# Lights-ctrl_rev02.net
KiCad netlist of a schematic drawn in EAGLE
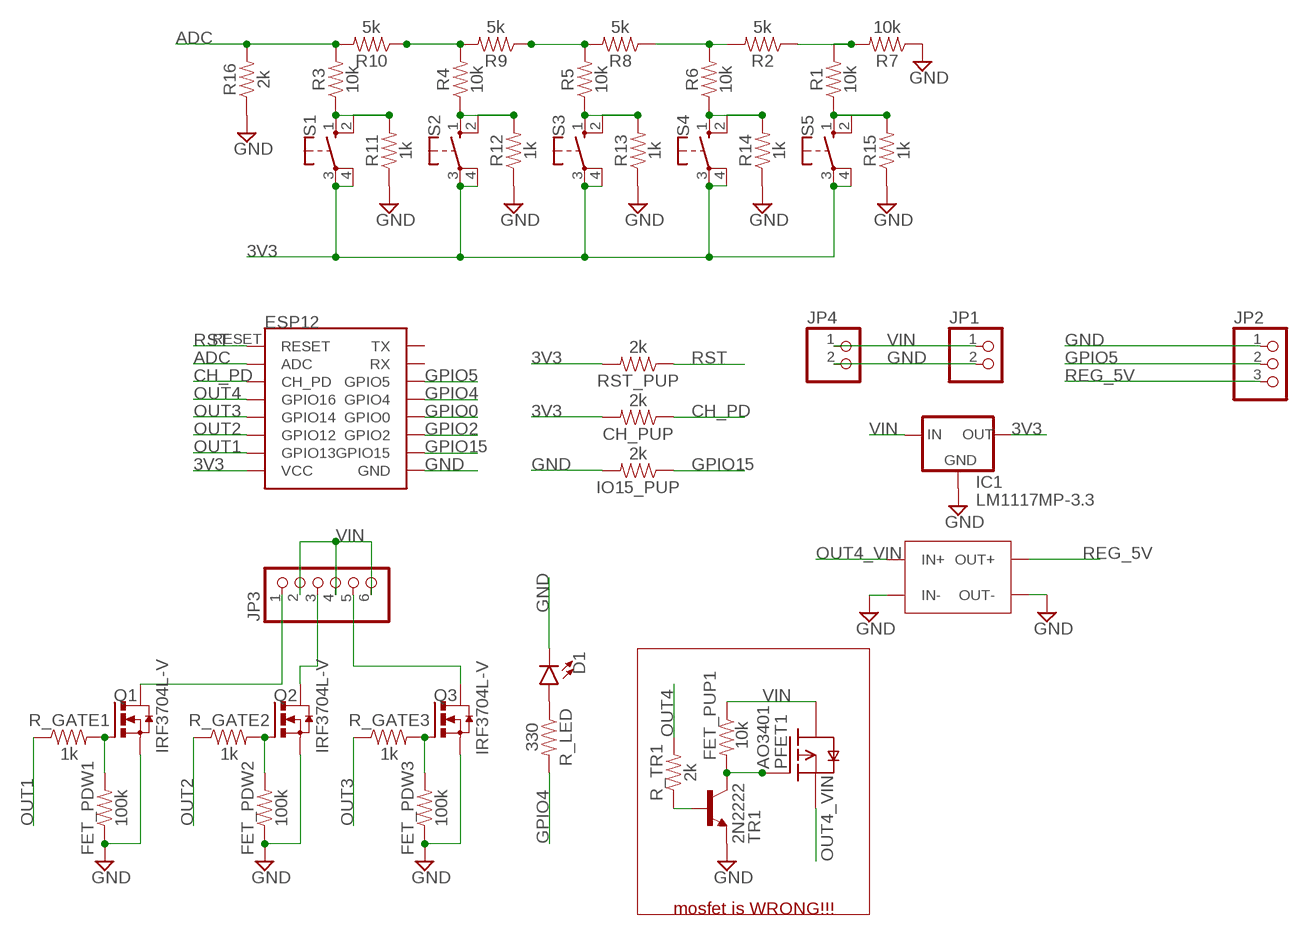
[diagram p0: schematic, sheet 1]

(export (version "E")
  (design (tool "Eeschema 10.0.6"))
  (components
    (comp (ref "CH_PUP")
      (value "2k")
      (footprint "eagle-import:0603")
      (libsource (lib "eagle-import") (part "200KOHM-0603-1/10W-1%"))
    )
    (comp (ref "D1")
      (value "LED5MM-KIT")
      (footprint "eagle-import:LED_5MM-KIT")
      (libsource (lib "eagle-import") (part "LED5MM-KIT"))
    )
    (comp (ref "FET_PDW1")
      (value "100k")
      (footprint "eagle-import:0603")
      (libsource (lib "eagle-import") (part "200KOHM-0603-1/10W-1%"))
    )
    (comp (ref "FET_PDW2")
      (value "100k")
      (footprint "eagle-import:0603")
      (libsource (lib "eagle-import") (part "200KOHM-0603-1/10W-1%"))
    )
    (comp (ref "FET_PDW3")
      (value "100k")
      (footprint "eagle-import:0603")
      (libsource (lib "eagle-import") (part "200KOHM-0603-1/10W-1%"))
    )
    (comp (ref "FET_PUP1")
      (value "10k")
      (footprint "eagle-import:0603")
      (libsource (lib "eagle-import") (part "200KOHM-0603-1/10W-1%"))
    )
    (comp (ref "IC1")
      (value "LM1117MP-3.3")
      (footprint "eagle-import:SOT223")
      (fields (field (name "MF") "Texas Instruments"))
      (libsource (lib "eagle-import") (part "LM1117?-MP3.3"))
    )
    (comp (ref "IO15_PUP")
      (value "2k")
      (footprint "eagle-import:0603")
      (libsource (lib "eagle-import") (part "200KOHM-0603-1/10W-1%"))
    )
    (comp (ref "JP1")
      (value "PINHD-1X2")
      (footprint "eagle-import:1X02")
      (libsource (lib "eagle-import") (part "PINHD-1X2"))
    )
    (comp (ref "JP2")
      (value "PINHD-1X3")
      (footprint "eagle-import:1X03")
      (libsource (lib "eagle-import") (part "PINHD-1X3"))
    )
    (comp (ref "JP3")
      (value "PINHD-1X6/90")
      (footprint "eagle-import:1X06_90")
      (libsource (lib "eagle-import") (part "PINHD-1X6/90"))
    )
    (comp (ref "JP4")
      (value "PINHD-1X2")
      (footprint "eagle-import:1X02")
      (libsource (lib "eagle-import") (part "PINHD-1X2"))
    )
    (comp (ref "PFET1")
      (value "AO3401")
      (footprint "eagle-import:SOT23-3")
      (fields (field (name "MF") "Alpha & Omega Semiconductor"))
      (libsource (lib "eagle-import") (part "AO3401"))
    )
    (comp (ref "Q1")
      (value "IRF3704L-V")
      (footprint "eagle-import:TO262-V")
      (libsource (lib "eagle-import") (part "IRF3704L-V"))
    )
    (comp (ref "Q2")
      (value "IRF3704L-V")
      (footprint "eagle-import:TO262-V")
      (libsource (lib "eagle-import") (part "IRF3704L-V"))
    )
    (comp (ref "Q3")
      (value "IRF3704L-V")
      (footprint "eagle-import:TO262-V")
      (libsource (lib "eagle-import") (part "IRF3704L-V"))
    )
    (comp (ref "R1")
      (value "10k")
      (footprint "eagle-import:0603")
      (libsource (lib "eagle-import") (part "200KOHM-0603-1/10W-1%"))
    )
    (comp (ref "R2")
      (value "5k")
      (footprint "eagle-import:0603")
      (libsource (lib "eagle-import") (part "200KOHM-0603-1/10W-1%"))
    )
    (comp (ref "R3")
      (value "10k")
      (footprint "eagle-import:0603")
      (libsource (lib "eagle-import") (part "200KOHM-0603-1/10W-1%"))
    )
    (comp (ref "R4")
      (value "10k")
      (footprint "eagle-import:0603")
      (libsource (lib "eagle-import") (part "200KOHM-0603-1/10W-1%"))
    )
    (comp (ref "R5")
      (value "10k")
      (footprint "eagle-import:0603")
      (libsource (lib "eagle-import") (part "200KOHM-0603-1/10W-1%"))
    )
    (comp (ref "R6")
      (value "10k")
      (footprint "eagle-import:0603")
      (libsource (lib "eagle-import") (part "200KOHM-0603-1/10W-1%"))
    )
    (comp (ref "R7")
      (value "10k")
      (footprint "eagle-import:0603")
      (libsource (lib "eagle-import") (part "200KOHM-0603-1/10W-1%"))
    )
    (comp (ref "R8")
      (value "5k")
      (footprint "eagle-import:0603")
      (libsource (lib "eagle-import") (part "200KOHM-0603-1/10W-1%"))
    )
    (comp (ref "R9")
      (value "5k")
      (footprint "eagle-import:0603")
      (libsource (lib "eagle-import") (part "200KOHM-0603-1/10W-1%"))
    )
    (comp (ref "R10")
      (value "5k")
      (footprint "eagle-import:0603")
      (libsource (lib "eagle-import") (part "200KOHM-0603-1/10W-1%"))
    )
    (comp (ref "R11")
      (value "1k")
      (footprint "eagle-import:0603")
      (libsource (lib "eagle-import") (part "200KOHM-0603-1/10W-1%"))
    )
    (comp (ref "R12")
      (value "1k")
      (footprint "eagle-import:0603")
      (libsource (lib "eagle-import") (part "200KOHM-0603-1/10W-1%"))
    )
    (comp (ref "R13")
      (value "1k")
      (footprint "eagle-import:0603")
      (libsource (lib "eagle-import") (part "200KOHM-0603-1/10W-1%"))
    )
    (comp (ref "R14")
      (value "1k")
      (footprint "eagle-import:0603")
      (libsource (lib "eagle-import") (part "200KOHM-0603-1/10W-1%"))
    )
    (comp (ref "R15")
      (value "1k")
      (footprint "eagle-import:0603")
      (libsource (lib "eagle-import") (part "200KOHM-0603-1/10W-1%"))
    )
    (comp (ref "R16")
      (value "2k")
      (footprint "eagle-import:0603")
      (libsource (lib "eagle-import") (part "200KOHM-0603-1/10W-1%"))
    )
    (comp (ref "RST_PUP")
      (value "2k")
      (footprint "eagle-import:0603")
      (libsource (lib "eagle-import") (part "200KOHM-0603-1/10W-1%"))
    )
    (comp (ref "R_GATE1")
      (value "1k")
      (footprint "eagle-import:0603")
      (libsource (lib "eagle-import") (part "200KOHM-0603-1/10W-1%"))
    )
    (comp (ref "R_GATE2")
      (value "1k")
      (footprint "eagle-import:0603")
      (libsource (lib "eagle-import") (part "200KOHM-0603-1/10W-1%"))
    )
    (comp (ref "R_GATE3")
      (value "1k")
      (footprint "eagle-import:0603")
      (libsource (lib "eagle-import") (part "200KOHM-0603-1/10W-1%"))
    )
    (comp (ref "R_LED")
      (value "330")
      (footprint "eagle-import:0603")
      (libsource (lib "eagle-import") (part "200KOHM-0603-1/10W-1%"))
    )
    (comp (ref "R_TR1")
      (value "2k")
      (footprint "eagle-import:0603")
      (libsource (lib "eagle-import") (part "200KOHM-0603-1/10W-1%"))
    )
    (comp (ref "S1")
      (value "10-XX")
      (footprint "eagle-import:B3F-10XX")
      (fields (field (name "MPN") "B3F-1000"))
      (libsource (lib "eagle-import") (part "10-XX"))
    )
    (comp (ref "S2")
      (value "10-XX")
      (footprint "eagle-import:B3F-10XX")
      (fields (field (name "MPN") "B3F-1000"))
      (libsource (lib "eagle-import") (part "10-XX"))
    )
    (comp (ref "S3")
      (value "10-XX")
      (footprint "eagle-import:B3F-10XX")
      (fields (field (name "MPN") "B3F-1000"))
      (libsource (lib "eagle-import") (part "10-XX"))
    )
    (comp (ref "S4")
      (value "10-XX")
      (footprint "eagle-import:B3F-10XX")
      (fields (field (name "MPN") "B3F-1000"))
      (libsource (lib "eagle-import") (part "10-XX"))
    )
    (comp (ref "S5")
      (value "10-XX")
      (footprint "eagle-import:B3F-10XX")
      (fields (field (name "MPN") "B3F-1000"))
      (libsource (lib "eagle-import") (part "10-XX"))
    )
    (comp (ref "TR1")
      (value "2N2222")
      (footprint "eagle-import:SOT23-BEC")
      (libsource (lib "eagle-import") (part "2N2222"))
    )
    (comp (ref "U$1")
      (value "ESP12E-CASTELLATED")
      (footprint "eagle-import:ESP12E-CASTELLATED")
      (libsource (lib "eagle-import") (part "ESP12E-CASTELLATED"))
    )
    (comp (ref "U$4")
      (value "XL4005")
      (footprint "eagle-import:XL4005")
      (libsource (lib "eagle-import") (part "XL4005"))
    )
  )
  (nets
    (net (code "1") (name "/3V3") (class "Default")
      (node (ref "CH_PUP") (pin "2") (pinfunction "2_2") (pintype "passive"))
      (node (ref "IC1") (pin "2") (pinfunction "OUT_2") (pintype "passive"))
      (node (ref "IC1") (pin "4") (pinfunction "OUT_4") (pintype "passive"))
      (node (ref "RST_PUP") (pin "2") (pinfunction "2_2") (pintype "passive"))
      (node (ref "S1") (pin "3") (pinfunction "P_3") (pintype "passive"))
      (node (ref "S1") (pin "4") (pinfunction "P1_4") (pintype "passive"))
      (node (ref "S2") (pin "3") (pinfunction "P_3") (pintype "passive"))
      (node (ref "S2") (pin "4") (pinfunction "P1_4") (pintype "passive"))
      (node (ref "S3") (pin "3") (pinfunction "P_3") (pintype "passive"))
      (node (ref "S3") (pin "4") (pinfunction "P1_4") (pintype "passive"))
      (node (ref "S4") (pin "3") (pinfunction "P_3") (pintype "passive"))
      (node (ref "S4") (pin "4") (pinfunction "P1_4") (pintype "passive"))
      (node (ref "S5") (pin "3") (pinfunction "P_3") (pintype "passive"))
      (node (ref "S5") (pin "4") (pinfunction "P1_4") (pintype "passive"))
      (node (ref "U$1") (pin "VCC") (pinfunction "VCC_VCC") (pintype "bidirectional"))
    )
    (net (code "2") (name "/ADC") (class "Default")
      (node (ref "R10") (pin "2") (pinfunction "2_2") (pintype "passive"))
      (node (ref "R16") (pin "2") (pinfunction "2_2") (pintype "passive"))
      (node (ref "R3") (pin "2") (pinfunction "2_2") (pintype "passive"))
      (node (ref "U$1") (pin "ADC") (pinfunction "ADC_ADC") (pintype "bidirectional"))
    )
    (net (code "3") (name "/CH_PD") (class "Default")
      (node (ref "CH_PUP") (pin "1") (pinfunction "1_1") (pintype "passive"))
      (node (ref "U$1") (pin "CH_PD") (pinfunction "CH_PD_CH_PD") (pintype "bidirectional"))
    )
    (net (code "4") (name "/GPIO0") (class "Default")
      (node (ref "U$1") (pin "GPIO0") (pinfunction "GPIO0_GPIO0") (pintype "bidirectional"))
    )
    (net (code "5") (name "/GPIO2") (class "Default")
      (node (ref "U$1") (pin "GPIO2") (pinfunction "GPIO2_GPIO2") (pintype "bidirectional"))
    )
    (net (code "6") (name "/GPIO4") (class "Default")
      (node (ref "R_LED") (pin "2") (pinfunction "2_2") (pintype "passive"))
      (node (ref "U$1") (pin "GPIO4") (pinfunction "GPIO4_GPIO4") (pintype "bidirectional"))
    )
    (net (code "7") (name "/GPIO5") (class "Default")
      (node (ref "JP2") (pin "2") (pinfunction "2_2") (pintype "passive"))
      (node (ref "U$1") (pin "GPIO5") (pinfunction "GPIO5_GPIO5") (pintype "bidirectional"))
    )
    (net (code "8") (name "/GPIO15") (class "Default")
      (node (ref "IO15_PUP") (pin "1") (pinfunction "1_1") (pintype "passive"))
      (node (ref "U$1") (pin "GPIO15") (pinfunction "GPIO15_GPIO15") (pintype "bidirectional"))
    )
    (net (code "9") (name "/OUT1") (class "Default")
      (node (ref "R_GATE1") (pin "1") (pinfunction "1_1") (pintype "passive"))
      (node (ref "U$1") (pin "GPIO13") (pinfunction "GPIO13_GPIO13") (pintype "bidirectional"))
    )
    (net (code "10") (name "/OUT2") (class "Default")
      (node (ref "R_GATE2") (pin "1") (pinfunction "1_1") (pintype "passive"))
      (node (ref "U$1") (pin "GPIO12") (pinfunction "GPIO12_GPIO12") (pintype "bidirectional"))
    )
    (net (code "11") (name "/OUT3") (class "Default")
      (node (ref "R_GATE3") (pin "1") (pinfunction "1_1") (pintype "passive"))
      (node (ref "U$1") (pin "GPIO14") (pinfunction "GPIO14_GPIO14") (pintype "bidirectional"))
    )
    (net (code "12") (name "/OUT4") (class "Default")
      (node (ref "R_TR1") (pin "2") (pinfunction "2_2") (pintype "passive"))
      (node (ref "U$1") (pin "GPIO16") (pinfunction "GPIO16_GPIO16") (pintype "bidirectional"))
    )
    (net (code "13") (name "/OUT4_VIN") (class "Default")
      (node (ref "PFET1") (pin "2") (pinfunction "S_2") (pintype "passive"))
      (node (ref "U$4") (pin "IN+") (pinfunction "IN+_IN+") (pintype "bidirectional"))
    )
    (net (code "14") (name "/REG_5V") (class "Default")
      (node (ref "JP2") (pin "3") (pinfunction "3_3") (pintype "passive"))
      (node (ref "U$4") (pin "OUT+") (pinfunction "OUT+_OUT+") (pintype "bidirectional"))
    )
    (net (code "15") (name "/RST") (class "Default")
      (node (ref "RST_PUP") (pin "1") (pinfunction "1_1") (pintype "passive"))
      (node (ref "U$1") (pin "RESET") (pinfunction "RESET_RESET") (pintype "bidirectional"))
    )
    (net (code "16") (name "/VIN") (class "Default")
      (node (ref "FET_PUP1") (pin "1") (pinfunction "1_1") (pintype "passive"))
      (node (ref "IC1") (pin "3") (pinfunction "IN_3") (pintype "input"))
      (node (ref "JP1") (pin "1") (pinfunction "1_1") (pintype "passive"))
      (node (ref "JP3") (pin "2") (pinfunction "2_2") (pintype "passive"))
      (node (ref "JP3") (pin "4") (pinfunction "4_4") (pintype "passive"))
      (node (ref "JP3") (pin "6") (pinfunction "6_6") (pintype "passive"))
      (node (ref "JP4") (pin "1") (pinfunction "1_1") (pintype "passive"))
      (node (ref "PFET1") (pin "3") (pinfunction "D_3") (pintype "passive"))
    )
    (net (code "17") (name "GND") (class "Default")
      (node (ref "D1") (pin "K") (pinfunction "C_K") (pintype "passive"))
      (node (ref "FET_PDW1") (pin "1") (pinfunction "1_1") (pintype "passive"))
      (node (ref "FET_PDW2") (pin "1") (pinfunction "1_1") (pintype "passive"))
      (node (ref "FET_PDW3") (pin "1") (pinfunction "1_1") (pintype "passive"))
      (node (ref "IC1") (pin "1") (pinfunction "GND_1") (pintype "input"))
      (node (ref "IO15_PUP") (pin "2") (pinfunction "2_2") (pintype "passive"))
      (node (ref "JP1") (pin "2") (pinfunction "2_2") (pintype "passive"))
      (node (ref "JP2") (pin "1") (pinfunction "1_1") (pintype "passive"))
      (node (ref "JP4") (pin "2") (pinfunction "2_2") (pintype "passive"))
      (node (ref "Q1") (pin "3") (pinfunction "S_3") (pintype "passive"))
      (node (ref "Q2") (pin "3") (pinfunction "S_3") (pintype "passive"))
      (node (ref "Q3") (pin "3") (pinfunction "S_3") (pintype "passive"))
      (node (ref "R11") (pin "1") (pinfunction "1_1") (pintype "passive"))
      (node (ref "R12") (pin "1") (pinfunction "1_1") (pintype "passive"))
      (node (ref "R13") (pin "1") (pinfunction "1_1") (pintype "passive"))
      (node (ref "R14") (pin "1") (pinfunction "1_1") (pintype "passive"))
      (node (ref "R15") (pin "1") (pinfunction "1_1") (pintype "passive"))
      (node (ref "R16") (pin "1") (pinfunction "1_1") (pintype "passive"))
      (node (ref "R7") (pin "1") (pinfunction "1_1") (pintype "passive"))
      (node (ref "TR1") (pin "E") (pinfunction "E_E") (pintype "passive"))
      (node (ref "U$1") (pin "GND") (pinfunction "GND_GND") (pintype "bidirectional"))
      (node (ref "U$4") (pin "IN-") (pinfunction "IN-_IN-") (pintype "bidirectional"))
      (node (ref "U$4") (pin "OUT-") (pinfunction "OUT-_OUT-") (pintype "bidirectional"))
    )
    (net (code "18") (name "Net-(D1-PadA)") (class "Default")
      (node (ref "D1") (pin "A") (pinfunction "A_A") (pintype "passive"))
      (node (ref "R_LED") (pin "1") (pinfunction "1_1") (pintype "passive"))
    )
    (net (code "19") (name "Net-(PFET1-G)") (class "Default")
      (node (ref "FET_PUP1") (pin "2") (pinfunction "2_2") (pintype "passive"))
      (node (ref "PFET1") (pin "1") (pinfunction "G_1") (pintype "passive"))
      (node (ref "TR1") (pin "C") (pinfunction "C_C") (pintype "passive"))
    )
    (net (code "20") (name "Net-(Q1-D)") (class "Default")
      (node (ref "JP3") (pin "1") (pinfunction "1_1") (pintype "passive"))
      (node (ref "Q1") (pin "2") (pinfunction "D_2") (pintype "passive"))
    )
    (net (code "21") (name "Net-(Q1-G)") (class "Default")
      (node (ref "FET_PDW1") (pin "2") (pinfunction "2_2") (pintype "passive"))
      (node (ref "Q1") (pin "1") (pinfunction "G_1") (pintype "passive"))
      (node (ref "R_GATE1") (pin "2") (pinfunction "2_2") (pintype "passive"))
    )
    (net (code "22") (name "Net-(Q2-D)") (class "Default")
      (node (ref "JP3") (pin "3") (pinfunction "3_3") (pintype "passive"))
      (node (ref "Q2") (pin "2") (pinfunction "D_2") (pintype "passive"))
    )
    (net (code "23") (name "Net-(Q2-G)") (class "Default")
      (node (ref "FET_PDW2") (pin "2") (pinfunction "2_2") (pintype "passive"))
      (node (ref "Q2") (pin "1") (pinfunction "G_1") (pintype "passive"))
      (node (ref "R_GATE2") (pin "2") (pinfunction "2_2") (pintype "passive"))
    )
    (net (code "24") (name "Net-(Q3-D)") (class "Default")
      (node (ref "JP3") (pin "5") (pinfunction "5_5") (pintype "passive"))
      (node (ref "Q3") (pin "2") (pinfunction "D_2") (pintype "passive"))
    )
    (net (code "25") (name "Net-(Q3-G)") (class "Default")
      (node (ref "FET_PDW3") (pin "2") (pinfunction "2_2") (pintype "passive"))
      (node (ref "Q3") (pin "1") (pinfunction "G_1") (pintype "passive"))
      (node (ref "R_GATE3") (pin "2") (pinfunction "2_2") (pintype "passive"))
    )
    (net (code "26") (name "Net-(R1-Pad2)") (class "Default")
      (node (ref "R1") (pin "2") (pinfunction "2_2") (pintype "passive"))
      (node (ref "R2") (pin "1") (pinfunction "1_1") (pintype "passive"))
      (node (ref "R7") (pin "2") (pinfunction "2_2") (pintype "passive"))
    )
    (net (code "27") (name "Net-(R2-Pad2)") (class "Default")
      (node (ref "R2") (pin "2") (pinfunction "2_2") (pintype "passive"))
      (node (ref "R6") (pin "2") (pinfunction "2_2") (pintype "passive"))
      (node (ref "R8") (pin "1") (pinfunction "1_1") (pintype "passive"))
    )
    (net (code "28") (name "Net-(R5-Pad2)") (class "Default")
      (node (ref "R5") (pin "2") (pinfunction "2_2") (pintype "passive"))
      (node (ref "R8") (pin "2") (pinfunction "2_2") (pintype "passive"))
      (node (ref "R9") (pin "1") (pinfunction "1_1") (pintype "passive"))
    )
    (net (code "29") (name "Net-(R10-Pad1)") (class "Default")
      (node (ref "R10") (pin "1") (pinfunction "1_1") (pintype "passive"))
      (node (ref "R4") (pin "2") (pinfunction "2_2") (pintype "passive"))
      (node (ref "R9") (pin "2") (pinfunction "2_2") (pintype "passive"))
    )
    (net (code "30") (name "Net-(R_TR1-Pad1)") (class "Default")
      (node (ref "R_TR1") (pin "1") (pinfunction "1_1") (pintype "passive"))
      (node (ref "TR1") (pin "B") (pinfunction "B_B") (pintype "passive"))
    )
    (net (code "31") (name "Net-(S1-S)") (class "Default")
      (node (ref "R11") (pin "2") (pinfunction "2_2") (pintype "passive"))
      (node (ref "R3") (pin "1") (pinfunction "1_1") (pintype "passive"))
      (node (ref "S1") (pin "1") (pinfunction "S_1") (pintype "passive"))
      (node (ref "S1") (pin "2") (pinfunction "S1_2") (pintype "passive"))
    )
    (net (code "32") (name "Net-(S2-S)") (class "Default")
      (node (ref "R12") (pin "2") (pinfunction "2_2") (pintype "passive"))
      (node (ref "R4") (pin "1") (pinfunction "1_1") (pintype "passive"))
      (node (ref "S2") (pin "1") (pinfunction "S_1") (pintype "passive"))
      (node (ref "S2") (pin "2") (pinfunction "S1_2") (pintype "passive"))
    )
    (net (code "33") (name "Net-(S3-S)") (class "Default")
      (node (ref "R13") (pin "2") (pinfunction "2_2") (pintype "passive"))
      (node (ref "R5") (pin "1") (pinfunction "1_1") (pintype "passive"))
      (node (ref "S3") (pin "1") (pinfunction "S_1") (pintype "passive"))
      (node (ref "S3") (pin "2") (pinfunction "S1_2") (pintype "passive"))
    )
    (net (code "34") (name "Net-(S4-S)") (class "Default")
      (node (ref "R14") (pin "2") (pinfunction "2_2") (pintype "passive"))
      (node (ref "R6") (pin "1") (pinfunction "1_1") (pintype "passive"))
      (node (ref "S4") (pin "1") (pinfunction "S_1") (pintype "passive"))
      (node (ref "S4") (pin "2") (pinfunction "S1_2") (pintype "passive"))
    )
    (net (code "35") (name "Net-(S5-S)") (class "Default")
      (node (ref "R1") (pin "1") (pinfunction "1_1") (pintype "passive"))
      (node (ref "R15") (pin "2") (pinfunction "2_2") (pintype "passive"))
      (node (ref "S5") (pin "1") (pinfunction "S_1") (pintype "passive"))
      (node (ref "S5") (pin "2") (pinfunction "S1_2") (pintype "passive"))
    )
    (net (code "36") (name "unconnected-(U$1-PadRX)") (class "Default")
      (node (ref "U$1") (pin "RX") (pinfunction "RX_RX") (pintype "bidirectional"))
    )
    (net (code "37") (name "unconnected-(U$1-PadTX)") (class "Default")
      (node (ref "U$1") (pin "TX") (pinfunction "TX_TX") (pintype "bidirectional"))
    )
  )
)
